# Clock_Extension.net
KiCad netlist of a schematic drawn in EAGLE
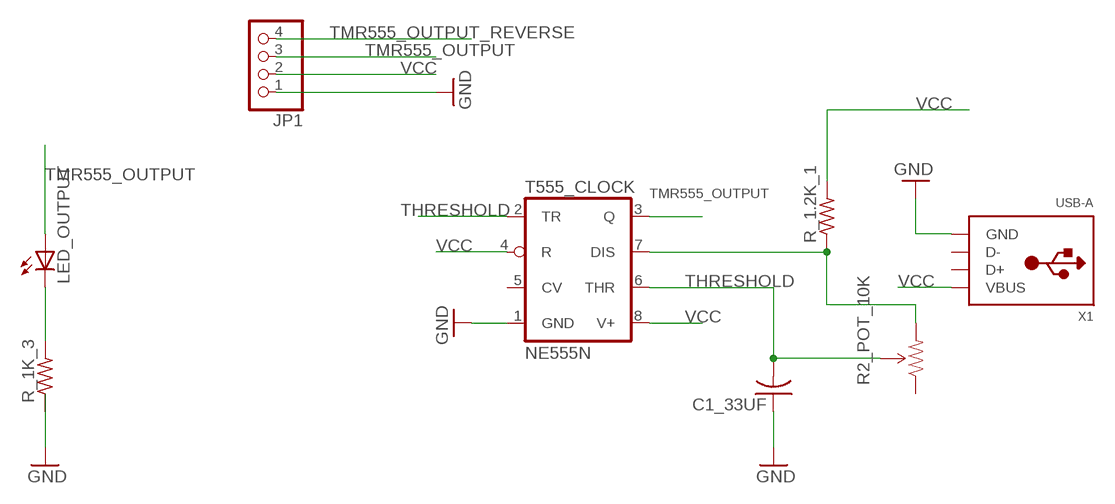
[diagram p0: schematic, sheet 1]

(export (version "E")
  (design (tool "Eeschema 10.0.6"))
  (components
    (comp (ref "C1_33UF")
      (value "C-US025-030X050")
      (footprint "eagle-import:C025-030X050")
      (libsource (lib "eagle-import") (part "C-US025-030X050"))
    )
    (comp (ref "JP1")
      (value "PINHD-1X4")
      (footprint "eagle-import:1X04")
      (libsource (lib "eagle-import") (part "PINHD-1X4"))
    )
    (comp (ref "LED_OUTPUT")
      (value "LEDSMT1206")
      (footprint "eagle-import:1206")
      (libsource (lib "eagle-import") (part "LEDSMT1206"))
    )
    (comp (ref "R2_POT_10K")
      (value "TRIMPOTPTH")
      (footprint "eagle-import:TRIM_POT_PTH")
      (libsource (lib "eagle-import") (part "TRIMPOTPTH"))
    )
    (comp (ref "R_1.2K_1")
      (value "R-US_R1206")
      (footprint "eagle-import:R1206")
      (libsource (lib "eagle-import") (part "R-US_R1206"))
    )
    (comp (ref "R_1K_3")
      (value "R-US_R1206")
      (footprint "eagle-import:R1206")
      (libsource (lib "eagle-import") (part "R-US_R1206"))
    )
    (comp (ref "T555_CLOCK")
      (value "NE555N")
      (footprint "eagle-import:DIL08")
      (libsource (lib "eagle-import") (part "555NNE"))
    )
    (comp (ref "X1")
      (value "USB-A")
      (footprint "eagle-import:MOLEX_480371000")
      (libsource (lib "eagle-import") (part "USB-A"))
    )
  )
  (nets
    (net (code "1") (name "/THRESHOLD") (class "Default")
      (node (ref "C1_33UF") (pin "2") (pinfunction "2_2") (pintype "passive"))
      (node (ref "R2_POT_10K") (pin "2") (pinfunction "WIPER_2") (pintype "passive"))
      (node (ref "T555_CLOCK") (pin "2") (pinfunction "TR_2") (pintype "input"))
      (node (ref "T555_CLOCK") (pin "6") (pinfunction "THR_6") (pintype "input"))
    )
    (net (code "2") (name "/TMR555_OUTPUT") (class "Default")
      (node (ref "JP1") (pin "3") (pinfunction "3_3") (pintype "passive"))
      (node (ref "LED_OUTPUT") (pin "A") (pinfunction "A_A") (pintype "passive"))
      (node (ref "T555_CLOCK") (pin "3") (pinfunction "Q_3") (pintype "output"))
    )
    (net (code "3") (name "/TMR555_OUTPUT_REVERSE") (class "Default")
      (node (ref "JP1") (pin "4") (pinfunction "4_4") (pintype "passive"))
    )
    (net (code "4") (name "/VCC") (class "Default")
      (node (ref "JP1") (pin "2") (pinfunction "2_2") (pintype "passive"))
      (node (ref "R_1.2K_1") (pin "2") (pinfunction "2_2") (pintype "passive"))
      (node (ref "T555_CLOCK") (pin "4") (pinfunction "R_4") (pintype "input"))
      (node (ref "T555_CLOCK") (pin "8") (pinfunction "V+_8") (pintype "power_in"))
      (node (ref "X1") (pin "1") (pinfunction "VBUS_1") (pintype "power_in"))
    )
    (net (code "5") (name "GND") (class "Default")
      (node (ref "C1_33UF") (pin "1") (pinfunction "1_1") (pintype "passive"))
      (node (ref "JP1") (pin "1") (pinfunction "1_1") (pintype "passive"))
      (node (ref "R_1K_3") (pin "1") (pinfunction "1_1") (pintype "passive"))
      (node (ref "T555_CLOCK") (pin "1") (pinfunction "GND_1") (pintype "power_in"))
      (node (ref "X1") (pin "4") (pinfunction "GND_4") (pintype "power_in"))
    )
    (net (code "6") (name "Net-(LED_OUTPUT-PadC)") (class "Default")
      (node (ref "LED_OUTPUT") (pin "C") (pinfunction "C_C") (pintype "passive"))
      (node (ref "R_1K_3") (pin "2") (pinfunction "2_2") (pintype "passive"))
    )
    (net (code "7") (name "Net-(R2_POT_10K-CW)") (class "Default")
      (node (ref "R2_POT_10K") (pin "3") (pinfunction "CW_3") (pintype "passive"))
      (node (ref "R_1.2K_1") (pin "1") (pinfunction "1_1") (pintype "passive"))
      (node (ref "T555_CLOCK") (pin "7") (pinfunction "DIS_7") (pintype "input"))
    )
    (net (code "8") (name "unconnected-(R2_POT_10K-CCW-Pad1)") (class "Default")
      (node (ref "R2_POT_10K") (pin "1") (pinfunction "CCW_1") (pintype "passive"))
    )
    (net (code "9") (name "unconnected-(T555_CLOCK-CV-Pad5)") (class "Default")
      (node (ref "T555_CLOCK") (pin "5") (pinfunction "CV_5") (pintype "input"))
    )
    (net (code "10") (name "unconnected-(X1-D+-Pad3)") (class "Default")
      (node (ref "X1") (pin "3") (pinfunction "D+_3") (pintype "bidirectional"))
    )
    (net (code "11") (name "unconnected-(X1-D--Pad2)") (class "Default")
      (node (ref "X1") (pin "2") (pinfunction "D-_2") (pintype "bidirectional"))
    )
  )
)
